# p1s-001.net
KiCad netlist of a schematic drawn in EAGLE
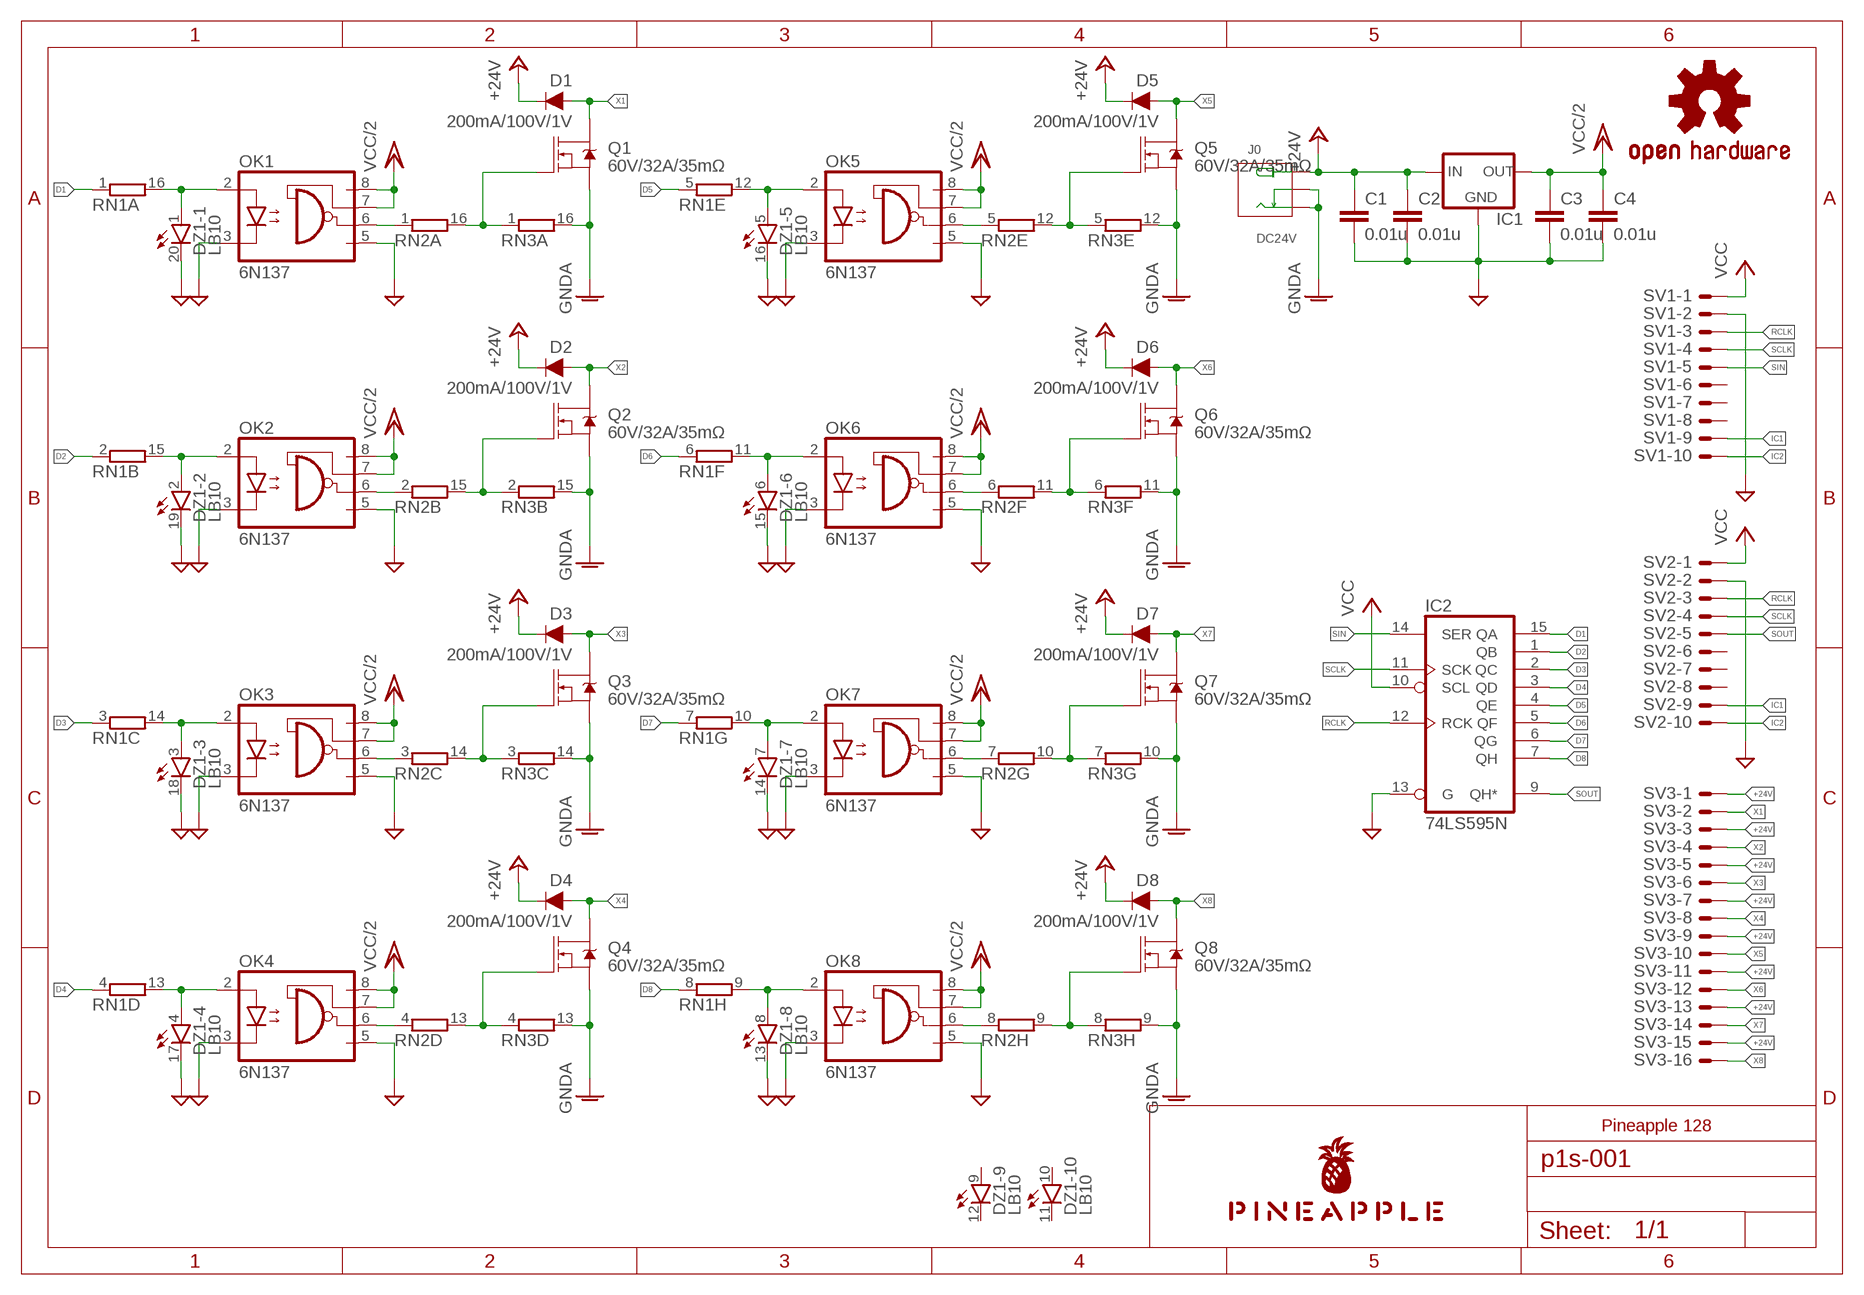
[diagram p0: schematic, sheet 1]

(export (version "E")
  (design (tool "Eeschema 10.0.6"))
  (components
    (comp (ref "C1")
      (value "0.01u")
      (footprint "eagle-import:C025-024X044")
      (libsource (lib "eagle-import") (part "C-EU025-024X044"))
    )
    (comp (ref "C2")
      (value "0.01u")
      (footprint "eagle-import:C025-024X044")
      (libsource (lib "eagle-import") (part "C-EU025-024X044"))
    )
    (comp (ref "C3")
      (value "0.01u")
      (footprint "eagle-import:C025-024X044")
      (libsource (lib "eagle-import") (part "C-EU025-024X044"))
    )
    (comp (ref "C4")
      (value "0.01u")
      (footprint "eagle-import:C025-024X044")
      (libsource (lib "eagle-import") (part "C-EU025-024X044"))
    )
    (comp (ref "D1")
      (value "200mA/100V/1V")
      (footprint "eagle-import:DIODE-1N4148")
      (libsource (lib "eagle-import") (part "DIODE-1N4148"))
    )
    (comp (ref "D2")
      (value "200mA/100V/1V")
      (footprint "eagle-import:DIODE-1N4148")
      (libsource (lib "eagle-import") (part "DIODE-1N4148"))
    )
    (comp (ref "D3")
      (value "200mA/100V/1V")
      (footprint "eagle-import:DIODE-1N4148")
      (libsource (lib "eagle-import") (part "DIODE-1N4148"))
    )
    (comp (ref "D4")
      (value "200mA/100V/1V")
      (footprint "eagle-import:DIODE-1N4148")
      (libsource (lib "eagle-import") (part "DIODE-1N4148"))
    )
    (comp (ref "D5")
      (value "200mA/100V/1V")
      (footprint "eagle-import:DIODE-1N4148")
      (libsource (lib "eagle-import") (part "DIODE-1N4148"))
    )
    (comp (ref "D6")
      (value "200mA/100V/1V")
      (footprint "eagle-import:DIODE-1N4148")
      (libsource (lib "eagle-import") (part "DIODE-1N4148"))
    )
    (comp (ref "D7")
      (value "200mA/100V/1V")
      (footprint "eagle-import:DIODE-1N4148")
      (libsource (lib "eagle-import") (part "DIODE-1N4148"))
    )
    (comp (ref "D8")
      (value "200mA/100V/1V")
      (footprint "eagle-import:DIODE-1N4148")
      (libsource (lib "eagle-import") (part "DIODE-1N4148"))
    )
    (comp (ref "DZ1")
      (value "LB10")
      (footprint "eagle-import:LB10")
      (libsource (lib "eagle-import") (part "LB10"))
    )
    (comp (ref "IC1")
      (value "78XXS")
      (footprint "eagle-import:78XXS")
      (libsource (lib "eagle-import") (part "78XXS"))
    )
    (comp (ref "IC2")
      (value "74LS595N")
      (footprint "eagle-import:DIL16")
      (libsource (lib "eagle-import") (part "74595NLS"))
    )
    (comp (ref "J0")
      (value "DC24V")
      (footprint "eagle-import:3P-L14.2_W11.0_H9.0MM")
      (libsource (lib "eagle-import") (part "JACK-DC-005'DC-005'"))
    )
    (comp (ref "LOGO1")
      (value "OSHW-LOGOS-COPPER")
      (footprint "eagle-import:OSHW-LOGO-S_COPPER")
      (libsource (lib "eagle-import") (part "OSHW-LOGOS-COPPER"))
    )
    (comp (ref "OK1")
      (value "6N137")
      (footprint "eagle-import:DIL08")
      (libsource (lib "eagle-import") (part "6N137"))
    )
    (comp (ref "OK2")
      (value "6N137")
      (footprint "eagle-import:DIL08")
      (libsource (lib "eagle-import") (part "6N137"))
    )
    (comp (ref "OK3")
      (value "6N137")
      (footprint "eagle-import:DIL08")
      (libsource (lib "eagle-import") (part "6N137"))
    )
    (comp (ref "OK4")
      (value "6N137")
      (footprint "eagle-import:DIL08")
      (libsource (lib "eagle-import") (part "6N137"))
    )
    (comp (ref "OK5")
      (value "6N137")
      (footprint "eagle-import:DIL08")
      (libsource (lib "eagle-import") (part "6N137"))
    )
    (comp (ref "OK6")
      (value "6N137")
      (footprint "eagle-import:DIL08")
      (libsource (lib "eagle-import") (part "6N137"))
    )
    (comp (ref "OK7")
      (value "6N137")
      (footprint "eagle-import:DIL08")
      (libsource (lib "eagle-import") (part "6N137"))
    )
    (comp (ref "OK8")
      (value "6N137")
      (footprint "eagle-import:DIL08")
      (libsource (lib "eagle-import") (part "6N137"))
    )
    (comp (ref "Q1")
      (value "60V/32A/35mΩ")
      (footprint "eagle-import:TO220V")
      (libsource (lib "eagle-import") (part "MOSFET-NCH-FQP30N06L"))
    )
    (comp (ref "Q2")
      (value "60V/32A/35mΩ")
      (footprint "eagle-import:TO220V")
      (libsource (lib "eagle-import") (part "MOSFET-NCH-FQP30N06L"))
    )
    (comp (ref "Q3")
      (value "60V/32A/35mΩ")
      (footprint "eagle-import:TO220V")
      (libsource (lib "eagle-import") (part "MOSFET-NCH-FQP30N06L"))
    )
    (comp (ref "Q4")
      (value "60V/32A/35mΩ")
      (footprint "eagle-import:TO220V")
      (libsource (lib "eagle-import") (part "MOSFET-NCH-FQP30N06L"))
    )
    (comp (ref "Q5")
      (value "60V/32A/35mΩ")
      (footprint "eagle-import:TO220V")
      (libsource (lib "eagle-import") (part "MOSFET-NCH-FQP30N06L"))
    )
    (comp (ref "Q6")
      (value "60V/32A/35mΩ")
      (footprint "eagle-import:TO220V")
      (libsource (lib "eagle-import") (part "MOSFET-NCH-FQP30N06L"))
    )
    (comp (ref "Q7")
      (value "60V/32A/35mΩ")
      (footprint "eagle-import:TO220V")
      (libsource (lib "eagle-import") (part "MOSFET-NCH-FQP30N06L"))
    )
    (comp (ref "Q8")
      (value "60V/32A/35mΩ")
      (footprint "eagle-import:TO220V")
      (libsource (lib "eagle-import") (part "MOSFET-NCH-FQP30N06L"))
    )
    (comp (ref "RN1")
      (value "8R-N")
      (footprint "eagle-import:DIL16")
      (libsource (lib "eagle-import") (part "8R-N"))
    )
    (comp (ref "RN2")
      (value "8R-N")
      (footprint "eagle-import:DIL16")
      (libsource (lib "eagle-import") (part "8R-N"))
    )
    (comp (ref "RN3")
      (value "8R-N")
      (footprint "eagle-import:DIL16")
      (libsource (lib "eagle-import") (part "8R-N"))
    )
    (comp (ref "SV1")
      (value "ML10LE")
      (footprint "eagle-import:ML10L")
      (libsource (lib "eagle-import") (part "ML10LE"))
    )
    (comp (ref "SV2")
      (value "ML10LE")
      (footprint "eagle-import:ML10L")
      (libsource (lib "eagle-import") (part "ML10LE"))
    )
    (comp (ref "SV3")
      (value "ML16LE")
      (footprint "eagle-import:ML16L")
      (libsource (lib "eagle-import") (part "ML16LE"))
    )
    (comp (ref "U$1")
      (value "PINEAPPLE450_SILK")
      (footprint "eagle-import:PINEAPPLE450_SILK")
      (libsource (lib "eagle-import") (part "PINEAPPLE450_SILK"))
    )
  )
  (nets
    (net (code "1") (name "+24V") (class "Default")
      (node (ref "C1") (pin "1") (pinfunction "1_1") (pintype "passive"))
      (node (ref "C2") (pin "1") (pinfunction "1_1") (pintype "passive"))
      (node (ref "D1") (pin "C") (pinfunction "C_C") (pintype "passive"))
      (node (ref "D2") (pin "C") (pinfunction "C_C") (pintype "passive"))
      (node (ref "D3") (pin "C") (pinfunction "C_C") (pintype "passive"))
      (node (ref "D4") (pin "C") (pinfunction "C_C") (pintype "passive"))
      (node (ref "D5") (pin "C") (pinfunction "C_C") (pintype "passive"))
      (node (ref "D6") (pin "C") (pinfunction "C_C") (pintype "passive"))
      (node (ref "D7") (pin "C") (pinfunction "C_C") (pintype "passive"))
      (node (ref "D8") (pin "C") (pinfunction "C_C") (pintype "passive"))
      (node (ref "IC1") (pin "IN") (pinfunction "IN_IN") (pintype "input"))
      (node (ref "J0") (pin "+") (pinfunction "+_+") (pintype "bidirectional"))
      (node (ref "SV3") (pin "1") (pinfunction "S_1") (pintype "passive"))
      (node (ref "SV3") (pin "11") (pinfunction "S_11") (pintype "passive"))
      (node (ref "SV3") (pin "13") (pinfunction "S_13") (pintype "passive"))
      (node (ref "SV3") (pin "15") (pinfunction "S_15") (pintype "passive"))
      (node (ref "SV3") (pin "3") (pinfunction "S_3") (pintype "passive"))
      (node (ref "SV3") (pin "5") (pinfunction "S_5") (pintype "passive"))
      (node (ref "SV3") (pin "7") (pinfunction "S_7") (pintype "passive"))
      (node (ref "SV3") (pin "9") (pinfunction "S_9") (pintype "passive"))
    )
    (net (code "2") (name "D1") (class "Default")
      (node (ref "IC2") (pin "15") (pinfunction "QA_15") (pintype "tri_state"))
      (node (ref "RN1") (pin "1") (pinfunction "1_1") (pintype "passive"))
    )
    (net (code "3") (name "D2") (class "Default")
      (node (ref "IC2") (pin "1") (pinfunction "QB_1") (pintype "tri_state"))
      (node (ref "RN1") (pin "2") (pinfunction "1_2") (pintype "passive"))
    )
    (net (code "4") (name "D3") (class "Default")
      (node (ref "IC2") (pin "2") (pinfunction "QC_2") (pintype "tri_state"))
      (node (ref "RN1") (pin "3") (pinfunction "1_3") (pintype "passive"))
    )
    (net (code "5") (name "D4") (class "Default")
      (node (ref "IC2") (pin "3") (pinfunction "QD_3") (pintype "tri_state"))
      (node (ref "RN1") (pin "4") (pinfunction "1_4") (pintype "passive"))
    )
    (net (code "6") (name "D5") (class "Default")
      (node (ref "IC2") (pin "4") (pinfunction "QE_4") (pintype "tri_state"))
      (node (ref "RN1") (pin "5") (pinfunction "1_5") (pintype "passive"))
    )
    (net (code "7") (name "D6") (class "Default")
      (node (ref "IC2") (pin "5") (pinfunction "QF_5") (pintype "tri_state"))
      (node (ref "RN1") (pin "6") (pinfunction "1_6") (pintype "passive"))
    )
    (net (code "8") (name "D7") (class "Default")
      (node (ref "IC2") (pin "6") (pinfunction "QG_6") (pintype "tri_state"))
      (node (ref "RN1") (pin "7") (pinfunction "1_7") (pintype "passive"))
    )
    (net (code "9") (name "D8") (class "Default")
      (node (ref "IC2") (pin "7") (pinfunction "QH_7") (pintype "tri_state"))
      (node (ref "RN1") (pin "8") (pinfunction "1_8") (pintype "passive"))
    )
    (net (code "10") (name "GND") (class "Default")
      (node (ref "C1") (pin "2") (pinfunction "2_2") (pintype "passive"))
      (node (ref "C2") (pin "2") (pinfunction "2_2") (pintype "passive"))
      (node (ref "C3") (pin "2") (pinfunction "2_2") (pintype "passive"))
      (node (ref "C4") (pin "2") (pinfunction "2_2") (pintype "passive"))
      (node (ref "DZ1") (pin "13") (pinfunction "C_13") (pintype "passive"))
      (node (ref "DZ1") (pin "14") (pinfunction "C_14") (pintype "passive"))
      (node (ref "DZ1") (pin "15") (pinfunction "C_15") (pintype "passive"))
      (node (ref "DZ1") (pin "16") (pinfunction "C_16") (pintype "passive"))
      (node (ref "DZ1") (pin "17") (pinfunction "C_17") (pintype "passive"))
      (node (ref "DZ1") (pin "18") (pinfunction "C_18") (pintype "passive"))
      (node (ref "DZ1") (pin "19") (pinfunction "C_19") (pintype "passive"))
      (node (ref "DZ1") (pin "20") (pinfunction "C_20") (pintype "passive"))
      (node (ref "IC1") (pin "GND") (pinfunction "GND_GND") (pintype "input"))
      (node (ref "IC2") (pin "13") (pinfunction "G_13") (pintype "input"))
      (node (ref "OK1") (pin "3") (pinfunction "C_3") (pintype "passive"))
      (node (ref "OK1") (pin "5") (pinfunction "GND_5") (pintype "passive"))
      (node (ref "OK2") (pin "3") (pinfunction "C_3") (pintype "passive"))
      (node (ref "OK2") (pin "5") (pinfunction "GND_5") (pintype "passive"))
      (node (ref "OK3") (pin "3") (pinfunction "C_3") (pintype "passive"))
      (node (ref "OK3") (pin "5") (pinfunction "GND_5") (pintype "passive"))
      (node (ref "OK4") (pin "3") (pinfunction "C_3") (pintype "passive"))
      (node (ref "OK4") (pin "5") (pinfunction "GND_5") (pintype "passive"))
      (node (ref "OK5") (pin "3") (pinfunction "C_3") (pintype "passive"))
      (node (ref "OK5") (pin "5") (pinfunction "GND_5") (pintype "passive"))
      (node (ref "OK6") (pin "3") (pinfunction "C_3") (pintype "passive"))
      (node (ref "OK6") (pin "5") (pinfunction "GND_5") (pintype "passive"))
      (node (ref "OK7") (pin "3") (pinfunction "C_3") (pintype "passive"))
      (node (ref "OK7") (pin "5") (pinfunction "GND_5") (pintype "passive"))
      (node (ref "OK8") (pin "3") (pinfunction "C_3") (pintype "passive"))
      (node (ref "OK8") (pin "5") (pinfunction "GND_5") (pintype "passive"))
      (node (ref "SV1") (pin "2") (pinfunction "S_2") (pintype "passive"))
      (node (ref "SV2") (pin "2") (pinfunction "S_2") (pintype "passive"))
    )
    (net (code "11") (name "GNDA") (class "Default")
      (node (ref "J0") (pin "-1") (pinfunction "-_-1") (pintype "bidirectional"))
      (node (ref "J0") (pin "-2") (pinfunction "CDN_-2") (pintype "bidirectional"))
      (node (ref "Q1") (pin "3") (pinfunction "S_3") (pintype "bidirectional"))
      (node (ref "Q2") (pin "3") (pinfunction "S_3") (pintype "bidirectional"))
      (node (ref "Q3") (pin "3") (pinfunction "S_3") (pintype "bidirectional"))
      (node (ref "Q4") (pin "3") (pinfunction "S_3") (pintype "bidirectional"))
      (node (ref "Q5") (pin "3") (pinfunction "S_3") (pintype "bidirectional"))
      (node (ref "Q6") (pin "3") (pinfunction "S_3") (pintype "bidirectional"))
      (node (ref "Q7") (pin "3") (pinfunction "S_3") (pintype "bidirectional"))
      (node (ref "Q8") (pin "3") (pinfunction "S_3") (pintype "bidirectional"))
      (node (ref "RN3") (pin "10") (pinfunction "2_10") (pintype "passive"))
      (node (ref "RN3") (pin "11") (pinfunction "2_11") (pintype "passive"))
      (node (ref "RN3") (pin "12") (pinfunction "2_12") (pintype "passive"))
      (node (ref "RN3") (pin "13") (pinfunction "2_13") (pintype "passive"))
      (node (ref "RN3") (pin "14") (pinfunction "2_14") (pintype "passive"))
      (node (ref "RN3") (pin "15") (pinfunction "2_15") (pintype "passive"))
      (node (ref "RN3") (pin "16") (pinfunction "2_16") (pintype "passive"))
      (node (ref "RN3") (pin "9") (pinfunction "2_9") (pintype "passive"))
    )
    (net (code "12") (name "IC1") (class "Default")
      (node (ref "SV1") (pin "9") (pinfunction "S_9") (pintype "passive"))
      (node (ref "SV2") (pin "9") (pinfunction "S_9") (pintype "passive"))
    )
    (net (code "13") (name "IC2") (class "Default")
      (node (ref "SV1") (pin "10") (pinfunction "S_10") (pintype "passive"))
      (node (ref "SV2") (pin "10") (pinfunction "S_10") (pintype "passive"))
    )
    (net (code "14") (name "Net-(DZ1A-A)") (class "Default")
      (node (ref "DZ1") (pin "1") (pinfunction "A_1") (pintype "passive"))
      (node (ref "OK1") (pin "2") (pinfunction "A_2") (pintype "passive"))
      (node (ref "RN1") (pin "16") (pinfunction "2_16") (pintype "passive"))
    )
    (net (code "15") (name "Net-(DZ1C-A)") (class "Default")
      (node (ref "DZ1") (pin "2") (pinfunction "A_2") (pintype "passive"))
      (node (ref "OK2") (pin "2") (pinfunction "A_2") (pintype "passive"))
      (node (ref "RN1") (pin "15") (pinfunction "2_15") (pintype "passive"))
    )
    (net (code "16") (name "Net-(DZ1D-A)") (class "Default")
      (node (ref "DZ1") (pin "3") (pinfunction "A_3") (pintype "passive"))
      (node (ref "OK3") (pin "2") (pinfunction "A_2") (pintype "passive"))
      (node (ref "RN1") (pin "14") (pinfunction "2_14") (pintype "passive"))
    )
    (net (code "17") (name "Net-(DZ1E-A)") (class "Default")
      (node (ref "DZ1") (pin "4") (pinfunction "A_4") (pintype "passive"))
      (node (ref "OK4") (pin "2") (pinfunction "A_2") (pintype "passive"))
      (node (ref "RN1") (pin "13") (pinfunction "2_13") (pintype "passive"))
    )
    (net (code "18") (name "Net-(DZ1F-A)") (class "Default")
      (node (ref "DZ1") (pin "5") (pinfunction "A_5") (pintype "passive"))
      (node (ref "OK5") (pin "2") (pinfunction "A_2") (pintype "passive"))
      (node (ref "RN1") (pin "12") (pinfunction "2_12") (pintype "passive"))
    )
    (net (code "19") (name "Net-(DZ1G-A)") (class "Default")
      (node (ref "DZ1") (pin "6") (pinfunction "A_6") (pintype "passive"))
      (node (ref "OK6") (pin "2") (pinfunction "A_2") (pintype "passive"))
      (node (ref "RN1") (pin "11") (pinfunction "2_11") (pintype "passive"))
    )
    (net (code "20") (name "Net-(DZ1H-A)") (class "Default")
      (node (ref "DZ1") (pin "7") (pinfunction "A_7") (pintype "passive"))
      (node (ref "OK7") (pin "2") (pinfunction "A_2") (pintype "passive"))
      (node (ref "RN1") (pin "10") (pinfunction "2_10") (pintype "passive"))
    )
    (net (code "21") (name "Net-(DZ1I-A)") (class "Default")
      (node (ref "DZ1") (pin "8") (pinfunction "A_8") (pintype "passive"))
      (node (ref "OK8") (pin "2") (pinfunction "A_2") (pintype "passive"))
      (node (ref "RN1") (pin "9") (pinfunction "2_9") (pintype "passive"))
    )
    (net (code "22") (name "Net-(OK1-VO)") (class "Default")
      (node (ref "OK1") (pin "6") (pinfunction "VO_6") (pintype "passive"))
      (node (ref "RN2") (pin "1") (pinfunction "1_1") (pintype "passive"))
    )
    (net (code "23") (name "Net-(OK2-VO)") (class "Default")
      (node (ref "OK2") (pin "6") (pinfunction "VO_6") (pintype "passive"))
      (node (ref "RN2") (pin "2") (pinfunction "1_2") (pintype "passive"))
    )
    (net (code "24") (name "Net-(OK3-VO)") (class "Default")
      (node (ref "OK3") (pin "6") (pinfunction "VO_6") (pintype "passive"))
      (node (ref "RN2") (pin "3") (pinfunction "1_3") (pintype "passive"))
    )
    (net (code "25") (name "Net-(OK4-VO)") (class "Default")
      (node (ref "OK4") (pin "6") (pinfunction "VO_6") (pintype "passive"))
      (node (ref "RN2") (pin "4") (pinfunction "1_4") (pintype "passive"))
    )
    (net (code "26") (name "Net-(OK5-VO)") (class "Default")
      (node (ref "OK5") (pin "6") (pinfunction "VO_6") (pintype "passive"))
      (node (ref "RN2") (pin "5") (pinfunction "1_5") (pintype "passive"))
    )
    (net (code "27") (name "Net-(OK6-VO)") (class "Default")
      (node (ref "OK6") (pin "6") (pinfunction "VO_6") (pintype "passive"))
      (node (ref "RN2") (pin "6") (pinfunction "1_6") (pintype "passive"))
    )
    (net (code "28") (name "Net-(OK7-VO)") (class "Default")
      (node (ref "OK7") (pin "6") (pinfunction "VO_6") (pintype "passive"))
      (node (ref "RN2") (pin "7") (pinfunction "1_7") (pintype "passive"))
    )
    (net (code "29") (name "Net-(OK8-VO)") (class "Default")
      (node (ref "OK8") (pin "6") (pinfunction "VO_6") (pintype "passive"))
      (node (ref "RN2") (pin "8") (pinfunction "1_8") (pintype "passive"))
    )
    (net (code "30") (name "Net-(Q1-G)") (class "Default")
      (node (ref "Q1") (pin "1") (pinfunction "G_1") (pintype "bidirectional"))
      (node (ref "RN2") (pin "16") (pinfunction "2_16") (pintype "passive"))
      (node (ref "RN3") (pin "1") (pinfunction "1_1") (pintype "passive"))
    )
    (net (code "31") (name "Net-(Q2-G)") (class "Default")
      (node (ref "Q2") (pin "1") (pinfunction "G_1") (pintype "bidirectional"))
      (node (ref "RN2") (pin "15") (pinfunction "2_15") (pintype "passive"))
      (node (ref "RN3") (pin "2") (pinfunction "1_2") (pintype "passive"))
    )
    (net (code "32") (name "Net-(Q3-G)") (class "Default")
      (node (ref "Q3") (pin "1") (pinfunction "G_1") (pintype "bidirectional"))
      (node (ref "RN2") (pin "14") (pinfunction "2_14") (pintype "passive"))
      (node (ref "RN3") (pin "3") (pinfunction "1_3") (pintype "passive"))
    )
    (net (code "33") (name "Net-(Q4-G)") (class "Default")
      (node (ref "Q4") (pin "1") (pinfunction "G_1") (pintype "bidirectional"))
      (node (ref "RN2") (pin "13") (pinfunction "2_13") (pintype "passive"))
      (node (ref "RN3") (pin "4") (pinfunction "1_4") (pintype "passive"))
    )
    (net (code "34") (name "Net-(Q5-G)") (class "Default")
      (node (ref "Q5") (pin "1") (pinfunction "G_1") (pintype "bidirectional"))
      (node (ref "RN2") (pin "12") (pinfunction "2_12") (pintype "passive"))
      (node (ref "RN3") (pin "5") (pinfunction "1_5") (pintype "passive"))
    )
    (net (code "35") (name "Net-(Q6-G)") (class "Default")
      (node (ref "Q6") (pin "1") (pinfunction "G_1") (pintype "bidirectional"))
      (node (ref "RN2") (pin "11") (pinfunction "2_11") (pintype "passive"))
      (node (ref "RN3") (pin "6") (pinfunction "1_6") (pintype "passive"))
    )
    (net (code "36") (name "Net-(Q7-G)") (class "Default")
      (node (ref "Q7") (pin "1") (pinfunction "G_1") (pintype "bidirectional"))
      (node (ref "RN2") (pin "10") (pinfunction "2_10") (pintype "passive"))
      (node (ref "RN3") (pin "7") (pinfunction "1_7") (pintype "passive"))
    )
    (net (code "37") (name "Net-(Q8-G)") (class "Default")
      (node (ref "Q8") (pin "1") (pinfunction "G_1") (pintype "bidirectional"))
      (node (ref "RN2") (pin "9") (pinfunction "2_9") (pintype "passive"))
      (node (ref "RN3") (pin "8") (pinfunction "1_8") (pintype "passive"))
    )
    (net (code "38") (name "RCLK") (class "Default")
      (node (ref "IC2") (pin "12") (pinfunction "RCK_12") (pintype "input"))
      (node (ref "SV1") (pin "3") (pinfunction "S_3") (pintype "passive"))
      (node (ref "SV2") (pin "3") (pinfunction "S_3") (pintype "passive"))
    )
    (net (code "39") (name "SCLK") (class "Default")
      (node (ref "IC2") (pin "11") (pinfunction "SCK_11") (pintype "input"))
      (node (ref "SV1") (pin "4") (pinfunction "S_4") (pintype "passive"))
      (node (ref "SV2") (pin "4") (pinfunction "S_4") (pintype "passive"))
    )
    (net (code "40") (name "SIN") (class "Default")
      (node (ref "IC2") (pin "14") (pinfunction "SER_14") (pintype "input"))
      (node (ref "SV1") (pin "5") (pinfunction "S_5") (pintype "passive"))
    )
    (net (code "41") (name "SOUT") (class "Default")
      (node (ref "IC2") (pin "9") (pinfunction "QH*_9") (pintype "tri_state"))
      (node (ref "SV2") (pin "5") (pinfunction "S_5") (pintype "passive"))
    )
    (net (code "42") (name "VCC") (class "Default")
      (node (ref "IC2") (pin "10") (pinfunction "SCL_10") (pintype "input"))
      (node (ref "SV1") (pin "1") (pinfunction "S_1") (pintype "passive"))
      (node (ref "SV2") (pin "1") (pinfunction "S_1") (pintype "passive"))
    )
    (net (code "43") (name "VCC{slash}2") (class "Default")
      (node (ref "C3") (pin "1") (pinfunction "1_1") (pintype "passive"))
      (node (ref "C4") (pin "1") (pinfunction "1_1") (pintype "passive"))
      (node (ref "IC1") (pin "OUT") (pinfunction "OUT_OUT") (pintype "passive"))
      (node (ref "OK1") (pin "7") (pinfunction "VE_7") (pintype "passive"))
      (node (ref "OK1") (pin "8") (pinfunction "VCC_8") (pintype "passive"))
      (node (ref "OK2") (pin "7") (pinfunction "VE_7") (pintype "passive"))
      (node (ref "OK2") (pin "8") (pinfunction "VCC_8") (pintype "passive"))
      (node (ref "OK3") (pin "7") (pinfunction "VE_7") (pintype "passive"))
      (node (ref "OK3") (pin "8") (pinfunction "VCC_8") (pintype "passive"))
      (node (ref "OK4") (pin "7") (pinfunction "VE_7") (pintype "passive"))
      (node (ref "OK4") (pin "8") (pinfunction "VCC_8") (pintype "passive"))
      (node (ref "OK5") (pin "7") (pinfunction "VE_7") (pintype "passive"))
      (node (ref "OK5") (pin "8") (pinfunction "VCC_8") (pintype "passive"))
      (node (ref "OK6") (pin "7") (pinfunction "VE_7") (pintype "passive"))
      (node (ref "OK6") (pin "8") (pinfunction "VCC_8") (pintype "passive"))
      (node (ref "OK7") (pin "7") (pinfunction "VE_7") (pintype "passive"))
      (node (ref "OK7") (pin "8") (pinfunction "VCC_8") (pintype "passive"))
      (node (ref "OK8") (pin "7") (pinfunction "VE_7") (pintype "passive"))
      (node (ref "OK8") (pin "8") (pinfunction "VCC_8") (pintype "passive"))
    )
    (net (code "44") (name "X1") (class "Default")
      (node (ref "D1") (pin "A") (pinfunction "A_A") (pintype "passive"))
      (node (ref "Q1") (pin "2") (pinfunction "D_2") (pintype "bidirectional"))
      (node (ref "SV3") (pin "2") (pinfunction "S_2") (pintype "passive"))
    )
    (net (code "45") (name "X2") (class "Default")
      (node (ref "D2") (pin "A") (pinfunction "A_A") (pintype "passive"))
      (node (ref "Q2") (pin "2") (pinfunction "D_2") (pintype "bidirectional"))
      (node (ref "SV3") (pin "4") (pinfunction "S_4") (pintype "passive"))
    )
    (net (code "46") (name "X3") (class "Default")
      (node (ref "D3") (pin "A") (pinfunction "A_A") (pintype "passive"))
      (node (ref "Q3") (pin "2") (pinfunction "D_2") (pintype "bidirectional"))
      (node (ref "SV3") (pin "6") (pinfunction "S_6") (pintype "passive"))
    )
    (net (code "47") (name "X4") (class "Default")
      (node (ref "D4") (pin "A") (pinfunction "A_A") (pintype "passive"))
      (node (ref "Q4") (pin "2") (pinfunction "D_2") (pintype "bidirectional"))
      (node (ref "SV3") (pin "8") (pinfunction "S_8") (pintype "passive"))
    )
    (net (code "48") (name "X5") (class "Default")
      (node (ref "D5") (pin "A") (pinfunction "A_A") (pintype "passive"))
      (node (ref "Q5") (pin "2") (pinfunction "D_2") (pintype "bidirectional"))
      (node (ref "SV3") (pin "10") (pinfunction "S_10") (pintype "passive"))
    )
    (net (code "49") (name "X6") (class "Default")
      (node (ref "D6") (pin "A") (pinfunction "A_A") (pintype "passive"))
      (node (ref "Q6") (pin "2") (pinfunction "D_2") (pintype "bidirectional"))
      (node (ref "SV3") (pin "12") (pinfunction "S_12") (pintype "passive"))
    )
    (net (code "50") (name "X7") (class "Default")
      (node (ref "D7") (pin "A") (pinfunction "A_A") (pintype "passive"))
      (node (ref "Q7") (pin "2") (pinfunction "D_2") (pintype "bidirectional"))
      (node (ref "SV3") (pin "14") (pinfunction "S_14") (pintype "passive"))
    )
    (net (code "51") (name "X8") (class "Default")
      (node (ref "D8") (pin "A") (pinfunction "A_A") (pintype "passive"))
      (node (ref "Q8") (pin "2") (pinfunction "D_2") (pintype "bidirectional"))
      (node (ref "SV3") (pin "16") (pinfunction "S_16") (pintype "passive"))
    )
    (net (code "52") (name "unconnected-(DZ1B-A-Pad10)") (class "Default")
      (node (ref "DZ1") (pin "10") (pinfunction "A_10") (pintype "passive"))
    )
    (net (code "53") (name "unconnected-(DZ1B-C-Pad11)") (class "Default")
      (node (ref "DZ1") (pin "11") (pinfunction "C_11") (pintype "passive"))
    )
    (net (code "54") (name "unconnected-(DZ1J-A-Pad9)") (class "Default")
      (node (ref "DZ1") (pin "9") (pinfunction "A_9") (pintype "passive"))
    )
    (net (code "55") (name "unconnected-(DZ1J-C-Pad12)") (class "Default")
      (node (ref "DZ1") (pin "12") (pinfunction "C_12") (pintype "passive"))
    )
    (net (code "56") (name "unconnected-(SV1G-S-Pad6)") (class "Default")
      (node (ref "SV1") (pin "6") (pinfunction "S_6") (pintype "passive"))
    )
    (net (code "57") (name "unconnected-(SV1H-S-Pad7)") (class "Default")
      (node (ref "SV1") (pin "7") (pinfunction "S_7") (pintype "passive"))
    )
    (net (code "58") (name "unconnected-(SV1I-S-Pad8)") (class "Default")
      (node (ref "SV1") (pin "8") (pinfunction "S_8") (pintype "passive"))
    )
    (net (code "59") (name "unconnected-(SV2G-S-Pad6)") (class "Default")
      (node (ref "SV2") (pin "6") (pinfunction "S_6") (pintype "passive"))
    )
    (net (code "60") (name "unconnected-(SV2H-S-Pad7)") (class "Default")
      (node (ref "SV2") (pin "7") (pinfunction "S_7") (pintype "passive"))
    )
    (net (code "61") (name "unconnected-(SV2I-S-Pad8)") (class "Default")
      (node (ref "SV2") (pin "8") (pinfunction "S_8") (pintype "passive"))
    )
  )
)
